# Metro_THM_LDO_Rev_C_-_CP2104.net
KiCad netlist of a schematic drawn in EAGLE
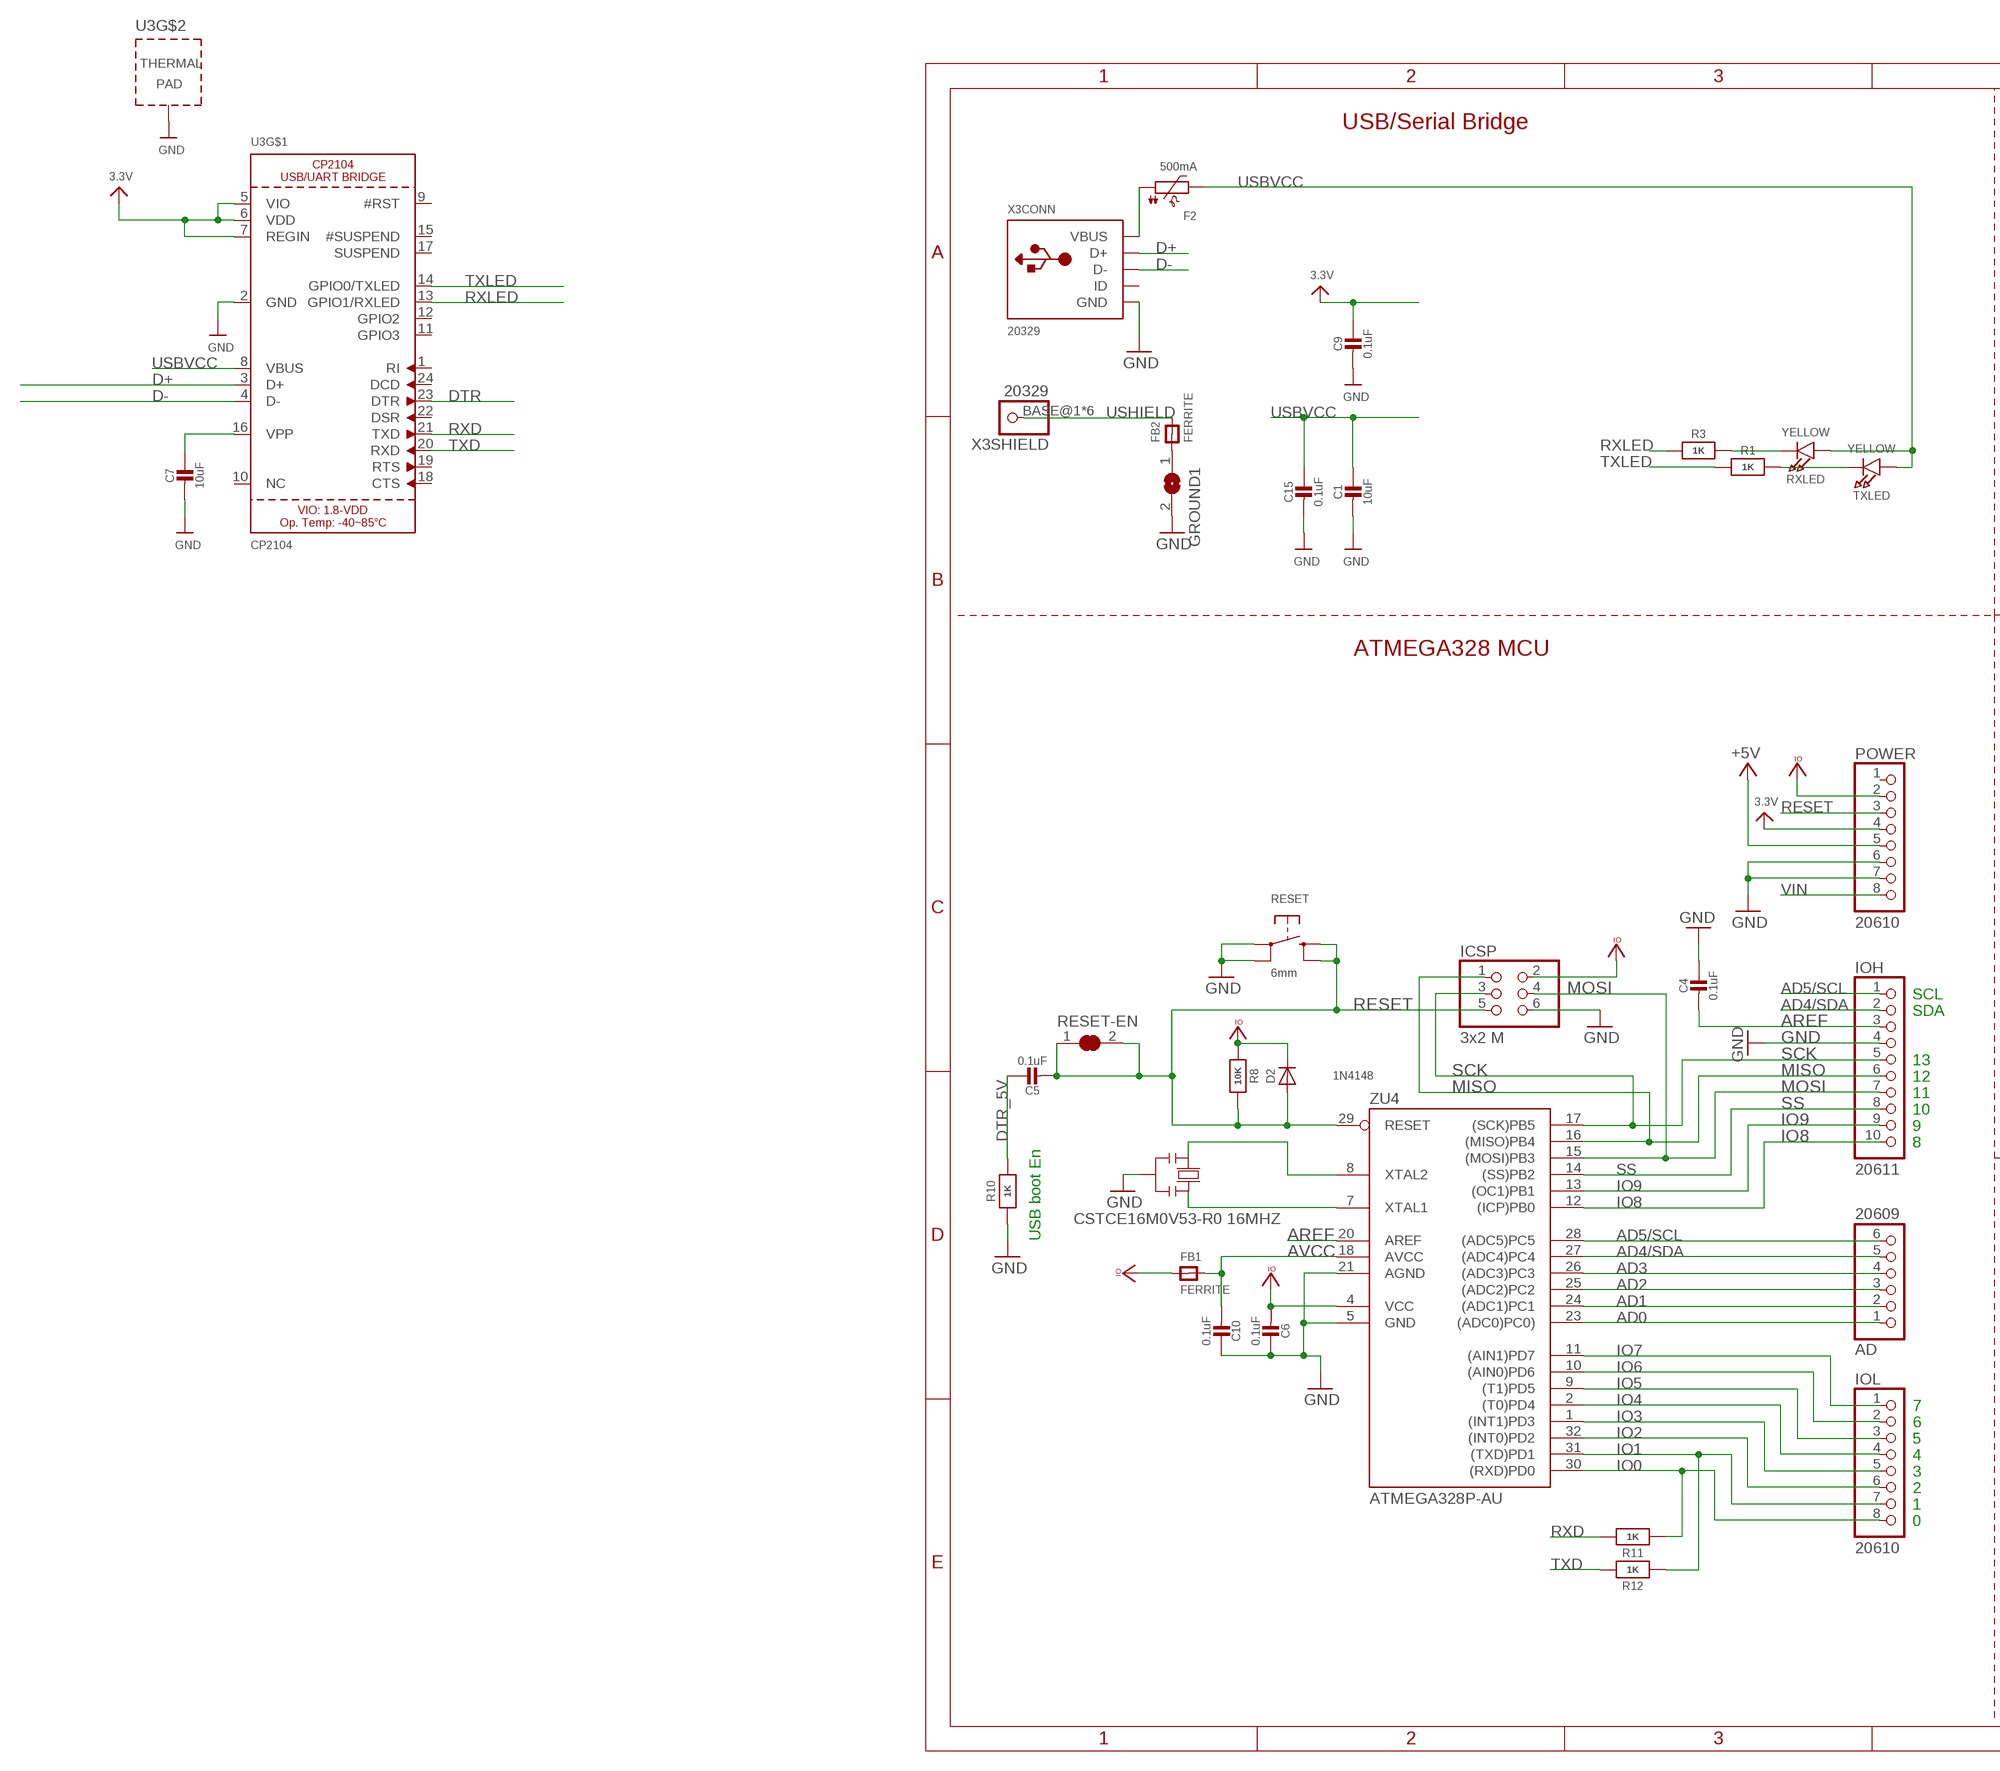
[diagram p0: schematic, sheet 1, part 1 of 2]
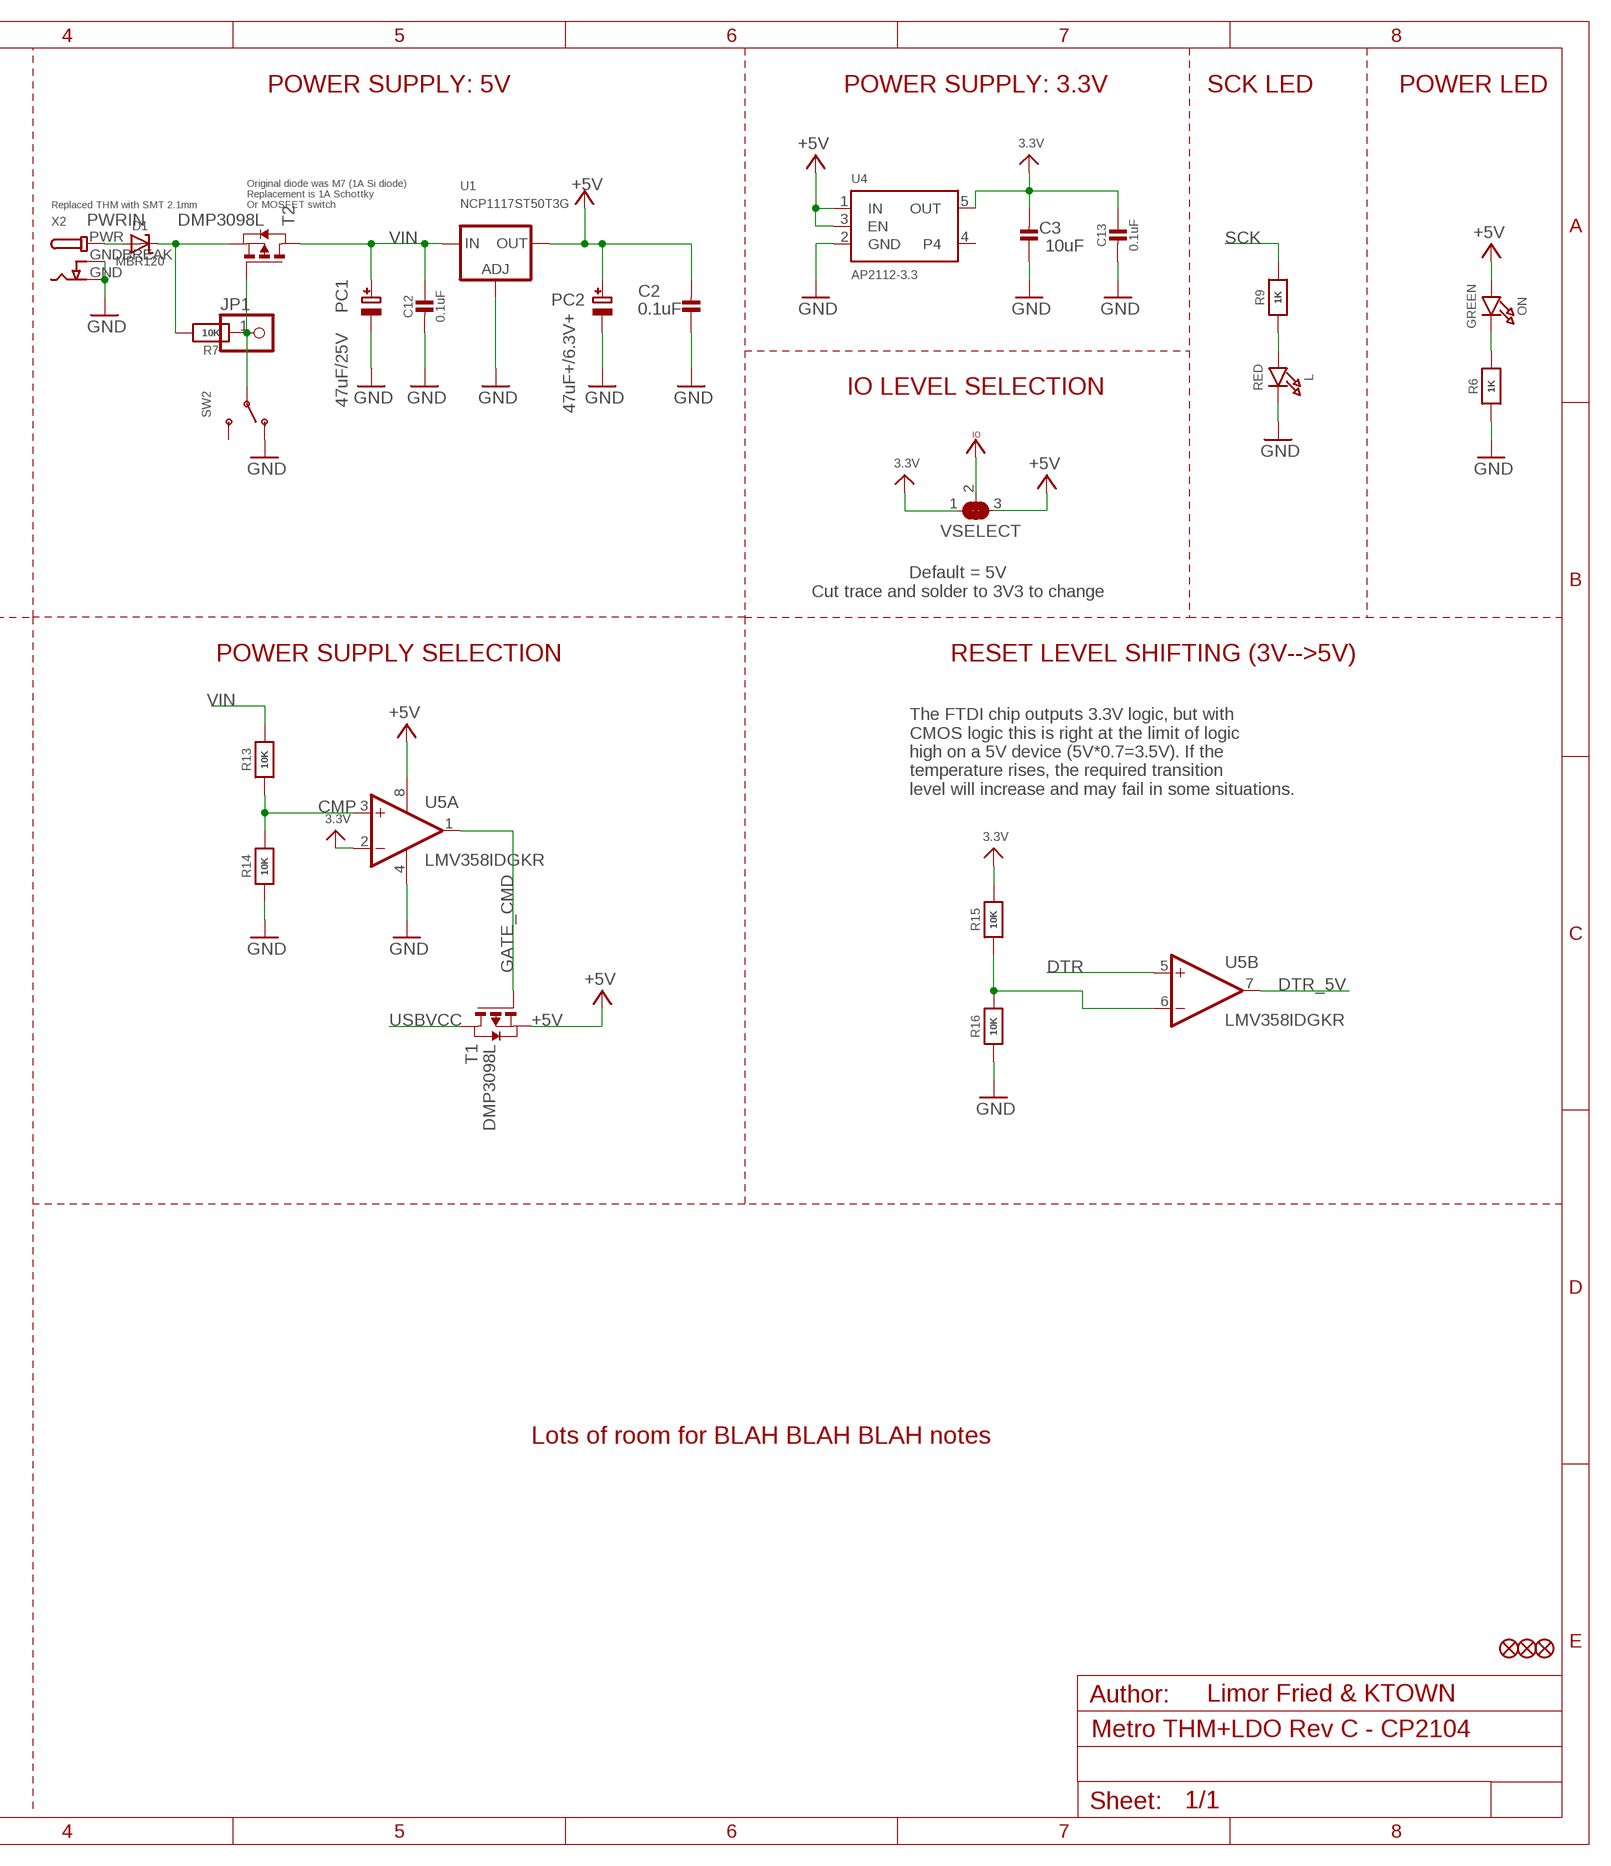
[diagram p1: schematic, sheet 1, part 2 of 2]

(export (version "E")
  (design (tool "Eeschema 10.0.6"))
  (components
    (comp (ref "AD")
      (value "20609")
      (footprint "eagle-import:1X06_OVAL")
      (libsource (lib "eagle-import") (part "HEADER-1X6"))
    )
    (comp (ref "C1")
      (value "10uF")
      (footprint "eagle-import:0805-NO")
      (libsource (lib "eagle-import") (part "CAP_CERAMIC0805-NOOUTLINE"))
    )
    (comp (ref "C2")
      (value "0.1uF")
      (footprint "eagle-import:0805-NO")
      (libsource (lib "eagle-import") (part "CAP_CERAMIC0805-NOOUTLINE"))
    )
    (comp (ref "C3")
      (value "10uF")
      (footprint "eagle-import:0805-NO")
      (libsource (lib "eagle-import") (part "CAP_CERAMIC0805-NOOUTLINE"))
    )
    (comp (ref "C4")
      (value "0.1uF")
      (footprint "eagle-import:0805-NO")
      (libsource (lib "eagle-import") (part "CAP_CERAMIC0805-NOOUTLINE"))
    )
    (comp (ref "C5")
      (value "0.1uF")
      (footprint "eagle-import:0805-NO")
      (libsource (lib "eagle-import") (part "CAP_CERAMIC0805-NOOUTLINE"))
    )
    (comp (ref "C6")
      (value "0.1uF")
      (footprint "eagle-import:0805-NO")
      (libsource (lib "eagle-import") (part "CAP_CERAMIC0805-NOOUTLINE"))
    )
    (comp (ref "C7")
      (value "10uF")
      (footprint "eagle-import:0805-NO")
      (libsource (lib "eagle-import") (part "CAP_CERAMIC0805-NOOUTLINE"))
    )
    (comp (ref "C9")
      (value "0.1uF")
      (footprint "eagle-import:0805-NO")
      (libsource (lib "eagle-import") (part "CAP_CERAMIC0805-NOOUTLINE"))
    )
    (comp (ref "C10")
      (value "0.1uF")
      (footprint "eagle-import:0805_10MGAP")
      (libsource (lib "eagle-import") (part "CAP_CERAMIC0805_10MGAP"))
    )
    (comp (ref "C12")
      (value "0.1uF")
      (footprint "eagle-import:0805-NO")
      (libsource (lib "eagle-import") (part "CAP_CERAMIC0805-NOOUTLINE"))
    )
    (comp (ref "C13")
      (value "0.1uF")
      (footprint "eagle-import:0805-NO")
      (libsource (lib "eagle-import") (part "CAP_CERAMIC0805-NOOUTLINE"))
    )
    (comp (ref "C15")
      (value "0.1uF")
      (footprint "eagle-import:0805-NO")
      (libsource (lib "eagle-import") (part "CAP_CERAMIC0805-NOOUTLINE"))
    )
    (comp (ref "D1")
      (value "MBR120")
      (footprint "eagle-import:SOD-123")
      (libsource (lib "eagle-import") (part "DIODE-SCHOTTKYSOD-123"))
    )
    (comp (ref "D2")
      (value "1N4148")
      (footprint "eagle-import:SOD-323")
      (libsource (lib "eagle-import") (part "DIODESOD-323"))
    )
    (comp (ref "F2")
      (value "500mA")
      (footprint "eagle-import:1206-NO")
      (libsource (lib "eagle-import") (part "PTC_1206NO"))
    )
    (comp (ref "FB1")
      (value "FERRITE")
      (footprint "eagle-import:0805-NO")
      (libsource (lib "eagle-import") (part "FERRITE-0805NO"))
    )
    (comp (ref "FB2")
      (value "FERRITE")
      (footprint "eagle-import:0805-NO")
      (libsource (lib "eagle-import") (part "FERRITE-0805NO"))
    )
    (comp (ref "FD1")
      (value "FIDUCIAL_1MM")
      (footprint "eagle-import:FIDUCIAL_1MM")
      (libsource (lib "eagle-import") (part "FIDUCIAL_1MM"))
    )
    (comp (ref "FD2")
      (value "FIDUCIAL_1MM")
      (footprint "eagle-import:FIDUCIAL_1MM")
      (libsource (lib "eagle-import") (part "FIDUCIAL_1MM"))
    )
    (comp (ref "FD3")
      (value "FIDUCIAL_1MM")
      (footprint "eagle-import:FIDUCIAL_1MM")
      (libsource (lib "eagle-import") (part "FIDUCIAL_1MM"))
    )
    (comp (ref "GROUND1")
      (value "SJ")
      (footprint "eagle-import:SJ")
      (libsource (lib "eagle-import") (part "SJ"))
    )
    (comp (ref "ICSP")
      (value "3x2 M")
      (footprint "eagle-import:2X03_ROUND_70MIL")
      (libsource (lib "eagle-import") (part "HEADER-2X3"))
    )
    (comp (ref "IOH")
      (value "20611")
      (footprint "eagle-import:1X10_OVAL")
      (libsource (lib "eagle-import") (part "HEADER-1X10"))
    )
    (comp (ref "IOL")
      (value "20610")
      (footprint "eagle-import:1X08_OVAL")
      (libsource (lib "eagle-import") (part "HEADER-1X8"))
    )
    (comp (ref "JP1")
      (value "HEADER-1X1ROUND")
      (footprint "eagle-import:1X01_ROUND")
      (libsource (lib "eagle-import") (part "HEADER-1X1ROUND"))
    )
    (comp (ref "L")
      (value "RED")
      (footprint "eagle-import:CHIPLED_0805_NOOUTLINE")
      (libsource (lib "eagle-import") (part "LED0805_NOOUTLINE"))
    )
    (comp (ref "ON")
      (value "GREEN")
      (footprint "eagle-import:CHIPLED_0805_NOOUTLINE")
      (libsource (lib "eagle-import") (part "LED0805_NOOUTLINE"))
    )
    (comp (ref "PC1")
      (value "47uF/25V")
      (footprint "eagle-import:PANASONIC_D")
      (libsource (lib "eagle-import") (part "CAP_ELECTROLYTICPANASONIC_D"))
    )
    (comp (ref "PC2")
      (value "47uF+/6.3V+")
      (footprint "eagle-import:PANASONIC_D")
      (libsource (lib "eagle-import") (part "CAP_ELECTROLYTICPANASONIC_D"))
    )
    (comp (ref "POWER")
      (value "20610")
      (footprint "eagle-import:1X08_OVAL")
      (libsource (lib "eagle-import") (part "HEADER-1X8"))
    )
    (comp (ref "R1")
      (value "1K")
      (footprint "eagle-import:0805-NO")
      (libsource (lib "eagle-import") (part "RESISTOR0805_NOOUTLINE"))
    )
    (comp (ref "R3")
      (value "1K")
      (footprint "eagle-import:0805-NO")
      (libsource (lib "eagle-import") (part "RESISTOR0805_NOOUTLINE"))
    )
    (comp (ref "R6")
      (value "1K")
      (footprint "eagle-import:0805-NO")
      (libsource (lib "eagle-import") (part "RESISTOR0805_NOOUTLINE"))
    )
    (comp (ref "R7")
      (value "10K")
      (footprint "eagle-import:0805-NO")
      (libsource (lib "eagle-import") (part "RESISTOR0805_NOOUTLINE"))
    )
    (comp (ref "R8")
      (value "10K")
      (footprint "eagle-import:_0805MP")
      (libsource (lib "eagle-import") (part "RESISTOR_0805MP"))
    )
    (comp (ref "R9")
      (value "1K")
      (footprint "eagle-import:0805-NO")
      (libsource (lib "eagle-import") (part "RESISTOR0805_NOOUTLINE"))
    )
    (comp (ref "R10")
      (value "1K")
      (footprint "eagle-import:0805-NO")
      (libsource (lib "eagle-import") (part "RESISTOR0805_NOOUTLINE"))
    )
    (comp (ref "R11")
      (value "1K")
      (footprint "eagle-import:0805-NO")
      (libsource (lib "eagle-import") (part "RESISTOR0805_NOOUTLINE"))
    )
    (comp (ref "R12")
      (value "1K")
      (footprint "eagle-import:0805-NO")
      (libsource (lib "eagle-import") (part "RESISTOR0805_NOOUTLINE"))
    )
    (comp (ref "R13")
      (value "10K")
      (footprint "eagle-import:0805-NO")
      (libsource (lib "eagle-import") (part "RESISTOR0805_NOOUTLINE"))
    )
    (comp (ref "R14")
      (value "10K")
      (footprint "eagle-import:0805-NO")
      (libsource (lib "eagle-import") (part "RESISTOR0805_NOOUTLINE"))
    )
    (comp (ref "R15")
      (value "10K")
      (footprint "eagle-import:0805-NO")
      (libsource (lib "eagle-import") (part "RESISTOR0805_NOOUTLINE"))
    )
    (comp (ref "R16")
      (value "10K")
      (footprint "eagle-import:0805-NO")
      (libsource (lib "eagle-import") (part "RESISTOR0805_NOOUTLINE"))
    )
    (comp (ref "RESET")
      (value "6mm")
      (footprint "eagle-import:EVQ-Q2")
      (libsource (lib "eagle-import") (part "SWITCH_TACT_SMT"))
    )
    (comp (ref "RESET-EN")
      (value "SOLDERJUMPER_CLOSED")
      (footprint "eagle-import:SOLDERJUMPER_CLOSEDWIRE")
      (libsource (lib "eagle-import") (part "SOLDERJUMPER_CLOSED"))
    )
    (comp (ref "RXLED")
      (value "YELLOW")
      (footprint "eagle-import:CHIPLED_0805_NOOUTLINE")
      (libsource (lib "eagle-import") (part "LED0805_NOOUTLINE"))
    )
    (comp (ref "SW2")
      (value "SWITCH_SPDT")
      (footprint "eagle-import:SPDT_SMT_SSSS811101")
      (libsource (lib "eagle-import") (part "SWITCH_SPDT"))
    )
    (comp (ref "T1")
      (value "DMP3098L")
      (footprint "eagle-import:SOT-23")
      (libsource (lib "eagle-import") (part "PMOSSOT23"))
    )
    (comp (ref "T2")
      (value "DMP3098L")
      (footprint "eagle-import:SOT-23")
      (libsource (lib "eagle-import") (part "PMOSSOT23"))
    )
    (comp (ref "TXLED")
      (value "YELLOW")
      (footprint "eagle-import:CHIPLED_0805_NOOUTLINE")
      (libsource (lib "eagle-import") (part "LED0805_NOOUTLINE"))
    )
    (comp (ref "U1")
      (value "NCP1117ST50T3G")
      (footprint "eagle-import:SOT223-R")
      (libsource (lib "eagle-import") (part "LM1117SOT223-REFLOW"))
    )
    (comp (ref "U3")
      (value "CP2104")
      (footprint "eagle-import:QFN24_4MM_SMSC")
      (libsource (lib "eagle-import") (part "CP2104"))
    )
    (comp (ref "U4")
      (value "AP2112-3.3")
      (footprint "eagle-import:SOT23-5")
      (libsource (lib "eagle-import") (part "VREG_SOT23-5"))
    )
    (comp (ref "U5")
      (value "LMV358IDGKR")
      (footprint "eagle-import:MSOP08")
      (libsource (lib "eagle-import") (part "LMV358?MMX"))
    )
    (comp (ref "VSELECT")
      (value "SOLDERJUMPER_2WAY")
      (footprint "eagle-import:SOLDERJUMPER_2WAY_OPEN_NOPASTE")
      (libsource (lib "eagle-import") (part "SOLDERJUMPER_2WAY"))
    )
    (comp (ref "X2")
      (value "DCBARRELPTH")
      (footprint "eagle-import:DCJACK_2MM_PTH")
      (libsource (lib "eagle-import") (part "DCBARRELPTH"))
    )
    (comp (ref "X3")
      (value "20329")
      (footprint "eagle-import:4UCONN_20329_V2")
      (libsource (lib "eagle-import") (part "USB_W_SHIELD_V2"))
    )
    (comp (ref "Y2")
      (value "CSTCE16M0V53-R0 16MHZ")
      (footprint "eagle-import:RESONATOR")
      (libsource (lib "eagle-import") (part "RESONATORMU"))
    )
    (comp (ref "ZU4")
      (value "ATMEGA328P-AU")
      (footprint "eagle-import:TQFP32-08")
      (libsource (lib "eagle-import") (part "ATMEGA328P-AU"))
    )
  )
  (nets
    (net (code "1") (name "+5V") (class "Default")
      (node (ref "C2") (pin "2") (pinfunction "2_2") (pintype "passive"))
      (node (ref "ON") (pin "A") (pinfunction "A_A") (pintype "passive"))
      (node (ref "PC2") (pin "+") (pinfunction "+_+") (pintype "passive"))
      (node (ref "POWER") (pin "5") (pinfunction "5_5") (pintype "passive"))
      (node (ref "T1") (pin "2") (pinfunction "S_2") (pintype "passive"))
      (node (ref "U1") (pin "2") (pinfunction "OUT_2") (pintype "passive"))
      (node (ref "U1") (pin "4") (pinfunction "OUT_4") (pintype "passive"))
      (node (ref "U4") (pin "1") (pinfunction "IN_1") (pintype "power_in"))
      (node (ref "U4") (pin "3") (pinfunction "EN_3") (pintype "input"))
      (node (ref "U5") (pin "8") (pinfunction "V+_8") (pintype "power_in"))
      (node (ref "VSELECT") (pin "3") (pinfunction "3_3") (pintype "passive"))
    )
    (net (code "2") (name "/AD0") (class "Default")
      (node (ref "AD") (pin "1") (pinfunction "1_1") (pintype "passive"))
      (node (ref "ZU4") (pin "23") (pinfunction "(ADC0)PC0)_23") (pintype "bidirectional"))
    )
    (net (code "3") (name "/AD1") (class "Default")
      (node (ref "AD") (pin "2") (pinfunction "2_2") (pintype "passive"))
      (node (ref "ZU4") (pin "24") (pinfunction "(ADC1)PC1_24") (pintype "bidirectional"))
    )
    (net (code "4") (name "/AD2") (class "Default")
      (node (ref "AD") (pin "3") (pinfunction "3_3") (pintype "passive"))
      (node (ref "ZU4") (pin "25") (pinfunction "(ADC2)PC2_25") (pintype "bidirectional"))
    )
    (net (code "5") (name "/AD3") (class "Default")
      (node (ref "AD") (pin "4") (pinfunction "4_4") (pintype "passive"))
      (node (ref "ZU4") (pin "26") (pinfunction "(ADC3)PC3_26") (pintype "bidirectional"))
    )
    (net (code "6") (name "/AD4{slash}SDA") (class "Default")
      (node (ref "AD") (pin "5") (pinfunction "5_5") (pintype "passive"))
      (node (ref "IOH") (pin "2") (pinfunction "2_2") (pintype "passive"))
      (node (ref "ZU4") (pin "27") (pinfunction "(ADC4)PC4_27") (pintype "bidirectional"))
    )
    (net (code "7") (name "/AD5{slash}SCL") (class "Default")
      (node (ref "AD") (pin "6") (pinfunction "6_6") (pintype "passive"))
      (node (ref "IOH") (pin "1") (pinfunction "1_1") (pintype "passive"))
      (node (ref "ZU4") (pin "28") (pinfunction "(ADC5)PC5_28") (pintype "bidirectional"))
    )
    (net (code "8") (name "/AREF") (class "Default")
      (node (ref "C4") (pin "2") (pinfunction "2_2") (pintype "passive"))
      (node (ref "IOH") (pin "3") (pinfunction "3_3") (pintype "passive"))
      (node (ref "ZU4") (pin "20") (pinfunction "AREF_20") (pintype "passive"))
    )
    (net (code "9") (name "/AVCC") (class "Default")
      (node (ref "C10") (pin "2") (pinfunction "2_2") (pintype "passive"))
      (node (ref "FB1") (pin "2") (pinfunction "P$2_2") (pintype "passive"))
      (node (ref "ZU4") (pin "18") (pinfunction "AVCC_18") (pintype "power_in"))
    )
    (net (code "10") (name "/CMP") (class "Default")
      (node (ref "R13") (pin "1") (pinfunction "1_1") (pintype "passive"))
      (node (ref "R14") (pin "2") (pinfunction "2_2") (pintype "passive"))
      (node (ref "U5") (pin "3") (pinfunction "+IN_3") (pintype "input"))
    )
    (net (code "11") (name "/D+") (class "Default")
      (node (ref "U3") (pin "3") (pinfunction "D+_3") (pintype "bidirectional"))
      (node (ref "X3") (pin "D+") (pinfunction "D+_D+") (pintype "bidirectional"))
    )
    (net (code "12") (name "/D-") (class "Default")
      (node (ref "U3") (pin "4") (pinfunction "D-_4") (pintype "bidirectional"))
      (node (ref "X3") (pin "D-") (pinfunction "D-_D-") (pintype "bidirectional"))
    )
    (net (code "13") (name "/DTR") (class "Default")
      (node (ref "U3") (pin "23") (pinfunction "DTR_23") (pintype "output"))
      (node (ref "U5") (pin "5") (pinfunction "+IN_5") (pintype "input"))
    )
    (net (code "14") (name "/DTR_5V") (class "Default")
      (node (ref "C5") (pin "1") (pinfunction "1_1") (pintype "passive"))
      (node (ref "R10") (pin "2") (pinfunction "2_2") (pintype "passive"))
      (node (ref "U5") (pin "7") (pinfunction "OUT_7") (pintype "output"))
    )
    (net (code "15") (name "/GATE_CMD") (class "Default")
      (node (ref "T1") (pin "3") (pinfunction "G_3") (pintype "passive"))
      (node (ref "U5") (pin "1") (pinfunction "OUT_1") (pintype "output"))
    )
    (net (code "16") (name "/IO0") (class "Default")
      (node (ref "IOL") (pin "8") (pinfunction "8_8") (pintype "passive"))
      (node (ref "R11") (pin "1") (pinfunction "1_1") (pintype "passive"))
      (node (ref "ZU4") (pin "30") (pinfunction "(RXD)PD0_30") (pintype "bidirectional"))
    )
    (net (code "17") (name "/IO1") (class "Default")
      (node (ref "IOL") (pin "7") (pinfunction "7_7") (pintype "passive"))
      (node (ref "R12") (pin "1") (pinfunction "1_1") (pintype "passive"))
      (node (ref "ZU4") (pin "31") (pinfunction "(TXD)PD1_31") (pintype "bidirectional"))
    )
    (net (code "18") (name "/IO2") (class "Default")
      (node (ref "IOL") (pin "6") (pinfunction "6_6") (pintype "passive"))
      (node (ref "ZU4") (pin "32") (pinfunction "(INT0)PD2_32") (pintype "bidirectional"))
    )
    (net (code "19") (name "/IO3") (class "Default")
      (node (ref "IOL") (pin "5") (pinfunction "5_5") (pintype "passive"))
      (node (ref "ZU4") (pin "1") (pinfunction "(INT1)PD3_1") (pintype "bidirectional"))
    )
    (net (code "20") (name "/IO4") (class "Default")
      (node (ref "IOL") (pin "4") (pinfunction "4_4") (pintype "passive"))
      (node (ref "ZU4") (pin "2") (pinfunction "(T0)PD4_2") (pintype "bidirectional"))
    )
    (net (code "21") (name "/IO5") (class "Default")
      (node (ref "IOL") (pin "3") (pinfunction "3_3") (pintype "passive"))
      (node (ref "ZU4") (pin "9") (pinfunction "(T1)PD5_9") (pintype "bidirectional"))
    )
    (net (code "22") (name "/IO6") (class "Default")
      (node (ref "IOL") (pin "2") (pinfunction "2_2") (pintype "passive"))
      (node (ref "ZU4") (pin "10") (pinfunction "(AIN0)PD6_10") (pintype "bidirectional"))
    )
    (net (code "23") (name "/IO7") (class "Default")
      (node (ref "IOL") (pin "1") (pinfunction "1_1") (pintype "passive"))
      (node (ref "ZU4") (pin "11") (pinfunction "(AIN1)PD7_11") (pintype "bidirectional"))
    )
    (net (code "24") (name "/IO8") (class "Default")
      (node (ref "IOH") (pin "10") (pinfunction "10_10") (pintype "passive"))
      (node (ref "ZU4") (pin "12") (pinfunction "(ICP)PB0_12") (pintype "bidirectional"))
    )
    (net (code "25") (name "/IO9") (class "Default")
      (node (ref "IOH") (pin "9") (pinfunction "9_9") (pintype "passive"))
      (node (ref "ZU4") (pin "13") (pinfunction "(OC1)PB1_13") (pintype "bidirectional"))
    )
    (net (code "26") (name "/MISO") (class "Default")
      (node (ref "ICSP") (pin "1") (pinfunction "1_1") (pintype "passive"))
      (node (ref "IOH") (pin "6") (pinfunction "6_6") (pintype "passive"))
      (node (ref "ZU4") (pin "16") (pinfunction "(MISO)PB4_16") (pintype "bidirectional"))
    )
    (net (code "27") (name "/MOSI") (class "Default")
      (node (ref "ICSP") (pin "4") (pinfunction "4_4") (pintype "passive"))
      (node (ref "IOH") (pin "7") (pinfunction "7_7") (pintype "passive"))
      (node (ref "ZU4") (pin "15") (pinfunction "(MOSI)PB3_15") (pintype "bidirectional"))
    )
    (net (code "28") (name "/PWRIN") (class "Default")
      (node (ref "D1") (pin "A") (pinfunction "A_A") (pintype "passive"))
      (node (ref "X2") (pin "PWR") (pinfunction "PWR_PWR") (pintype "power_in"))
    )
    (net (code "29") (name "/RESET") (class "Default")
      (node (ref "C5") (pin "2") (pinfunction "2_2") (pintype "passive"))
      (node (ref "D2") (pin "A") (pinfunction "A_A") (pintype "passive"))
      (node (ref "ICSP") (pin "5") (pinfunction "5_5") (pintype "passive"))
      (node (ref "POWER") (pin "3") (pinfunction "3_3") (pintype "passive"))
      (node (ref "R8") (pin "1") (pinfunction "1_1") (pintype "passive"))
      (node (ref "RESET") (pin "B") (pinfunction "S_B") (pintype "passive"))
      (node (ref "RESET") (pin "B'") (pinfunction "S1_B'") (pintype "passive"))
      (node (ref "RESET-EN") (pin "1") (pinfunction "1_1") (pintype "passive"))
      (node (ref "RESET-EN") (pin "2") (pinfunction "2_2") (pintype "passive"))
      (node (ref "ZU4") (pin "29") (pinfunction "RESET_29") (pintype "input"))
    )
    (net (code "30") (name "/RXD") (class "Default")
      (node (ref "R11") (pin "2") (pinfunction "2_2") (pintype "passive"))
      (node (ref "U3") (pin "21") (pinfunction "TXD_21") (pintype "output"))
    )
    (net (code "31") (name "/RXLED") (class "Default")
      (node (ref "R3") (pin "2") (pinfunction "2_2") (pintype "passive"))
      (node (ref "U3") (pin "13") (pinfunction "GPIO1/RXLED_13") (pintype "bidirectional"))
    )
    (net (code "32") (name "/SCK") (class "Default")
      (node (ref "ICSP") (pin "3") (pinfunction "3_3") (pintype "passive"))
      (node (ref "IOH") (pin "5") (pinfunction "5_5") (pintype "passive"))
      (node (ref "R9") (pin "2") (pinfunction "2_2") (pintype "passive"))
      (node (ref "ZU4") (pin "17") (pinfunction "(SCK)PB5_17") (pintype "bidirectional"))
    )
    (net (code "33") (name "/SS") (class "Default")
      (node (ref "IOH") (pin "8") (pinfunction "8_8") (pintype "passive"))
      (node (ref "ZU4") (pin "14") (pinfunction "(SS)PB2_14") (pintype "bidirectional"))
    )
    (net (code "34") (name "/TXD") (class "Default")
      (node (ref "R12") (pin "2") (pinfunction "2_2") (pintype "passive"))
      (node (ref "U3") (pin "20") (pinfunction "RXD_20") (pintype "input"))
    )
    (net (code "35") (name "/TXLED") (class "Default")
      (node (ref "R1") (pin "2") (pinfunction "2_2") (pintype "passive"))
      (node (ref "U3") (pin "14") (pinfunction "GPIO0/TXLED_14") (pintype "bidirectional"))
    )
    (net (code "36") (name "/USBVCC") (class "Default")
      (node (ref "C1") (pin "1") (pinfunction "1_1") (pintype "passive"))
      (node (ref "C15") (pin "1") (pinfunction "1_1") (pintype "passive"))
      (node (ref "F2") (pin "2") (pinfunction "2_2") (pintype "passive"))
      (node (ref "RXLED") (pin "A") (pinfunction "A_A") (pintype "passive"))
      (node (ref "T1") (pin "1") (pinfunction "D_1") (pintype "passive"))
      (node (ref "TXLED") (pin "A") (pinfunction "A_A") (pintype "passive"))
      (node (ref "U3") (pin "8") (pinfunction "VBUS_8") (pintype "power_in"))
    )
    (net (code "37") (name "/USHIELD") (class "Default")
      (node (ref "FB2") (pin "2") (pinfunction "P$2_2") (pintype "passive"))
      (node (ref "X3") (pin "BASE@1") (pinfunction "1_BASE@1") (pintype "passive"))
      (node (ref "X3") (pin "BASE@2") (pinfunction "1_BASE@2") (pintype "passive"))
      (node (ref "X3") (pin "SPRT@1") (pinfunction "1_SPRT@1") (pintype "passive"))
      (node (ref "X3") (pin "SPRT@2") (pinfunction "1_SPRT@2") (pintype "passive"))
      (node (ref "X3") (pin "SPRT@3") (pinfunction "1_SPRT@3") (pintype "passive"))
      (node (ref "X3") (pin "SPRT@4") (pinfunction "1_SPRT@4") (pintype "passive"))
    )
    (net (code "38") (name "/VIN") (class "Default")
      (node (ref "C12") (pin "1") (pinfunction "1_1") (pintype "passive"))
      (node (ref "PC1") (pin "+") (pinfunction "+_+") (pintype "passive"))
      (node (ref "POWER") (pin "8") (pinfunction "8_8") (pintype "passive"))
      (node (ref "R13") (pin "2") (pinfunction "2_2") (pintype "passive"))
      (node (ref "T2") (pin "1") (pinfunction "D_1") (pintype "passive"))
      (node (ref "U1") (pin "3") (pinfunction "IN_3") (pintype "input"))
    )
    (net (code "39") (name "3.3V") (class "Default")
      (node (ref "C13") (pin "1") (pinfunction "1_1") (pintype "passive"))
      (node (ref "C3") (pin "2") (pinfunction "2_2") (pintype "passive"))
      (node (ref "C9") (pin "1") (pinfunction "1_1") (pintype "passive"))
      (node (ref "POWER") (pin "4") (pinfunction "4_4") (pintype "passive"))
      (node (ref "R15") (pin "2") (pinfunction "2_2") (pintype "passive"))
      (node (ref "U3") (pin "5") (pinfunction "VIO_5") (pintype "power_in"))
      (node (ref "U3") (pin "6") (pinfunction "VDD_6") (pintype "power_in"))
      (node (ref "U3") (pin "7") (pinfunction "REGIN_7") (pintype "power_in"))
      (node (ref "U4") (pin "5") (pinfunction "OUT_5") (pintype "power_in"))
      (node (ref "U5") (pin "2") (pinfunction "-IN_2") (pintype "input"))
      (node (ref "VSELECT") (pin "1") (pinfunction "1_1") (pintype "passive"))
    )
    (net (code "40") (name "GND") (class "Default")
      (node (ref "C1") (pin "2") (pinfunction "2_2") (pintype "passive"))
      (node (ref "C10") (pin "1") (pinfunction "1_1") (pintype "passive"))
      (node (ref "C12") (pin "2") (pinfunction "2_2") (pintype "passive"))
      (node (ref "C13") (pin "2") (pinfunction "2_2") (pintype "passive"))
      (node (ref "C15") (pin "2") (pinfunction "2_2") (pintype "passive"))
      (node (ref "C2") (pin "1") (pinfunction "1_1") (pintype "passive"))
      (node (ref "C3") (pin "1") (pinfunction "1_1") (pintype "passive"))
      (node (ref "C4") (pin "1") (pinfunction "1_1") (pintype "passive"))
      (node (ref "C6") (pin "1") (pinfunction "1_1") (pintype "passive"))
      (node (ref "C7") (pin "2") (pinfunction "2_2") (pintype "passive"))
      (node (ref "C9") (pin "2") (pinfunction "2_2") (pintype "passive"))
      (node (ref "GROUND1") (pin "2") (pinfunction "2_2") (pintype "passive"))
      (node (ref "ICSP") (pin "6") (pinfunction "6_6") (pintype "passive"))
      (node (ref "IOH") (pin "4") (pinfunction "4_4") (pintype "passive"))
      (node (ref "L") (pin "C") (pinfunction "C_C") (pintype "passive"))
      (node (ref "PC1") (pin "-") (pinfunction "-_-") (pintype "passive"))
      (node (ref "PC2") (pin "-") (pinfunction "-_-") (pintype "passive"))
      (node (ref "POWER") (pin "6") (pinfunction "6_6") (pintype "passive"))
      (node (ref "POWER") (pin "7") (pinfunction "7_7") (pintype "passive"))
      (node (ref "R10") (pin "1") (pinfunction "1_1") (pintype "passive"))
      (node (ref "R14") (pin "1") (pinfunction "1_1") (pintype "passive"))
      (node (ref "R16") (pin "1") (pinfunction "1_1") (pintype "passive"))
      (node (ref "R6") (pin "1") (pinfunction "1_1") (pintype "passive"))
      (node (ref "RESET") (pin "A") (pinfunction "P_A") (pintype "passive"))
      (node (ref "RESET") (pin "A'") (pinfunction "P1_A'") (pintype "passive"))
      (node (ref "SW2") (pin "A") (pinfunction "O_A") (pintype "passive"))
      (node (ref "U1") (pin "1") (pinfunction "ADJ_1") (pintype "input"))
      (node (ref "U3") (pin "2") (pinfunction "GND_2") (pintype "power_in"))
      (node (ref "U3") (pin "THERM") (pinfunction "TP_THERM") (pintype "power_in"))
      (node (ref "U4") (pin "2") (pinfunction "GND_2") (pintype "power_in"))
      (node (ref "U5") (pin "4") (pinfunction "V-_4") (pintype "power_in"))
      (node (ref "X2") (pin "GND") (pinfunction "GND_GND") (pintype "power_in"))
      (node (ref "X2") (pin "GNDBREAK") (pinfunction "GNDBREAK_GNDBREAK") (pintype "power_in"))
      (node (ref "X3") (pin "GND") (pinfunction "GND_GND") (pintype "power_in"))
      (node (ref "Y2") (pin "2") (pinfunction "2_2") (pintype "passive"))
      (node (ref "ZU4") (pin "21") (pinfunction "AGND_21") (pintype "power_in"))
      (node (ref "ZU4") (pin "5") (pinfunction "GND_5") (pintype "power_in"))
    )
    (net (code "41") (name "Net-(F2-Pad1)") (class "Default")
      (node (ref "F2") (pin "1") (pinfunction "1_1") (pintype "passive"))
      (node (ref "X3") (pin "VBUS") (pinfunction "VBUS_VBUS") (pintype "power_in"))
    )
    (net (code "42") (name "Net-(FB2-P$1)") (class "Default")
      (node (ref "FB2") (pin "1") (pinfunction "P$1_1") (pintype "passive"))
      (node (ref "GROUND1") (pin "1") (pinfunction "1_1") (pintype "passive"))
    )
    (net (code "43") (name "Net-(L-PadA)") (class "Default")
      (node (ref "L") (pin "A") (pinfunction "A_A") (pintype "passive"))
      (node (ref "R9") (pin "1") (pinfunction "1_1") (pintype "passive"))
    )
    (net (code "44") (name "Net-(ON-PadC)") (class "Default")
      (node (ref "ON") (pin "C") (pinfunction "C_C") (pintype "passive"))
      (node (ref "R6") (pin "2") (pinfunction "2_2") (pintype "passive"))
    )
    (net (code "45") (name "Net-(R1-Pad1)") (class "Default")
      (node (ref "R1") (pin "1") (pinfunction "1_1") (pintype "passive"))
      (node (ref "TXLED") (pin "C") (pinfunction "C_C") (pintype "passive"))
    )
    (net (code "46") (name "Net-(R3-Pad1)") (class "Default")
      (node (ref "R3") (pin "1") (pinfunction "1_1") (pintype "passive"))
      (node (ref "RXLED") (pin "C") (pinfunction "C_C") (pintype "passive"))
    )
    (net (code "47") (name "Net-(SW2-P)") (class "Default")
      (node (ref "JP1") (pin "1") (pinfunction "1_1") (pintype "passive"))
      (node (ref "R7") (pin "1") (pinfunction "1_1") (pintype "passive"))
      (node (ref "SW2") (pin "B") (pinfunction "P_B") (pintype "passive"))
      (node (ref "T2") (pin "3") (pinfunction "G_3") (pintype "passive"))
    )
    (net (code "48") (name "Net-(T2-S)") (class "Default")
      (node (ref "D1") (pin "C") (pinfunction "C_C") (pintype "passive"))
      (node (ref "R7") (pin "2") (pinfunction "2_2") (pintype "passive"))
      (node (ref "T2") (pin "2") (pinfunction "S_2") (pintype "passive"))
    )
    (net (code "49") (name "Net-(U3A-VPP)") (class "Default")
      (node (ref "C7") (pin "1") (pinfunction "1_1") (pintype "passive"))
      (node (ref "U3") (pin "16") (pinfunction "VPP_16") (pintype "bidirectional"))
    )
    (net (code "50") (name "Net-(U5B--IN)") (class "Default")
      (node (ref "R15") (pin "1") (pinfunction "1_1") (pintype "passive"))
      (node (ref "R16") (pin "2") (pinfunction "2_2") (pintype "passive"))
      (node (ref "U5") (pin "6") (pinfunction "-IN_6") (pintype "input"))
    )
    (net (code "51") (name "Net-(ZU4-XTAL1)") (class "Default")
      (node (ref "Y2") (pin "3") (pinfunction "3_3") (pintype "passive"))
      (node (ref "ZU4") (pin "7") (pinfunction "XTAL1_7") (pintype "bidirectional"))
    )
    (net (code "52") (name "Net-(ZU4-XTAL2)") (class "Default")
      (node (ref "Y2") (pin "1") (pinfunction "1_1") (pintype "passive"))
      (node (ref "ZU4") (pin "8") (pinfunction "XTAL2_8") (pintype "bidirectional"))
    )
    (net (code "53") (name "VCCIO") (class "Default")
      (node (ref "C6") (pin "2") (pinfunction "2_2") (pintype "passive"))
      (node (ref "D2") (pin "C") (pinfunction "C_C") (pintype "passive"))
      (node (ref "FB1") (pin "1") (pinfunction "P$1_1") (pintype "passive"))
      (node (ref "ICSP") (pin "2") (pinfunction "2_2") (pintype "passive"))
      (node (ref "POWER") (pin "2") (pinfunction "2_2") (pintype "passive"))
      (node (ref "R8") (pin "2") (pinfunction "2_2") (pintype "passive"))
      (node (ref "VSELECT") (pin "2") (pinfunction "2_2") (pintype "passive"))
      (node (ref "ZU4") (pin "4") (pinfunction "VCC_4") (pintype "power_in"))
    )
    (net (code "54") (name "unconnected-(POWER-Pad1)") (class "Default")
      (node (ref "POWER") (pin "1") (pinfunction "1_1") (pintype "passive"))
    )
    (net (code "55") (name "unconnected-(SW2-S-PadC)") (class "Default")
      (node (ref "SW2") (pin "C") (pinfunction "S_C") (pintype "passive"))
    )
    (net (code "56") (name "unconnected-(U3A-#RST-Pad9)") (class "Default")
      (node (ref "U3") (pin "9") (pinfunction "#RST_9") (pintype "bidirectional"))
    )
    (net (code "57") (name "unconnected-(U3A-#SUSPEND-Pad15)") (class "Default")
      (node (ref "U3") (pin "15") (pinfunction "#SUSPEND_15") (pintype "output"))
    )
    (net (code "58") (name "unconnected-(U3A-CTS-Pad18)") (class "Default")
      (node (ref "U3") (pin "18") (pinfunction "CTS_18") (pintype "input"))
    )
    (net (code "59") (name "unconnected-(U3A-DCD-Pad24)") (class "Default")
      (node (ref "U3") (pin "24") (pinfunction "DCD_24") (pintype "input"))
    )
    (net (code "60") (name "unconnected-(U3A-DSR-Pad22)") (class "Default")
      (node (ref "U3") (pin "22") (pinfunction "DSR_22") (pintype "input"))
    )
    (net (code "61") (name "unconnected-(U3A-GPIO2-Pad12)") (class "Default")
      (node (ref "U3") (pin "12") (pinfunction "GPIO2_12") (pintype "bidirectional"))
    )
    (net (code "62") (name "unconnected-(U3A-GPIO3-Pad11)") (class "Default")
      (node (ref "U3") (pin "11") (pinfunction "GPIO3_11") (pintype "bidirectional"))
    )
    (net (code "63") (name "unconnected-(U3A-NC-Pad10)") (class "Default")
      (node (ref "U3") (pin "10") (pinfunction "NC_10") (pintype "no_connect"))
    )
    (net (code "64") (name "unconnected-(U3A-RI-Pad1)") (class "Default")
      (node (ref "U3") (pin "1") (pinfunction "RI_1") (pintype "input"))
    )
    (net (code "65") (name "unconnected-(U3A-RTS-Pad19)") (class "Default")
      (node (ref "U3") (pin "19") (pinfunction "RTS_19") (pintype "output"))
    )
    (net (code "66") (name "unconnected-(U3A-SUSPEND-Pad17)") (class "Default")
      (node (ref "U3") (pin "17") (pinfunction "SUSPEND_17") (pintype "output"))
    )
    (net (code "67") (name "unconnected-(U4-P4-Pad4)") (class "Default")
      (node (ref "U4") (pin "4") (pinfunction "P4_4") (pintype "bidirectional"))
    )
    (net (code "68") (name "unconnected-(X3-PadID)") (class "Default")
      (node (ref "X3") (pin "ID") (pinfunction "ID_ID") (pintype "bidirectional"))
    )
  )
)
